# Audio_Codec.net
KiCad netlist of a schematic drawn in Altium Designer
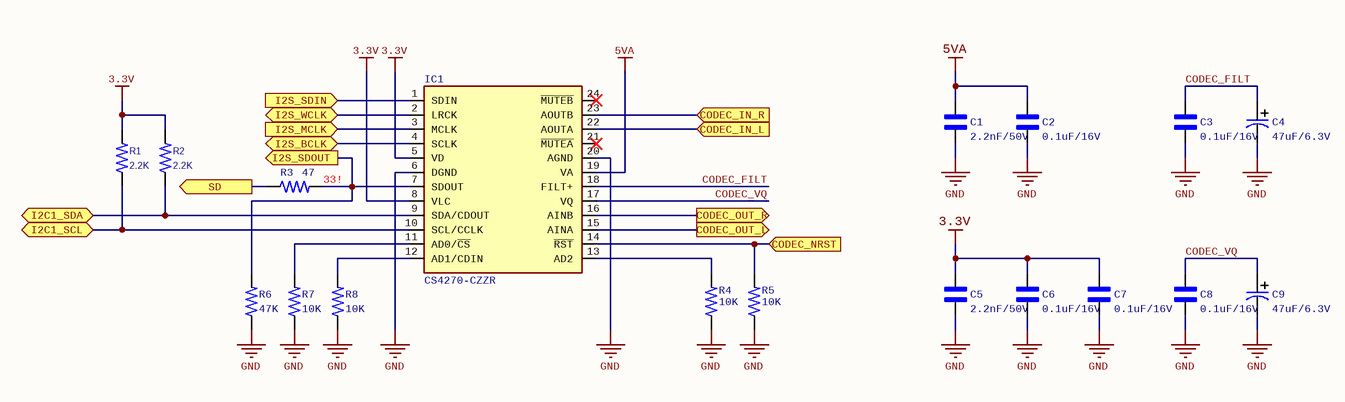
[diagram p0: Audio Codec.SchDoc]

(export (version "E")
  (design (tool "Eeschema 10.0.6"))
  (components
    (comp (ref "C1")
      (value "2.2nF/50V")
      (footprint "C0603")
      (description "MLCC 2.2nF 10V X5R 10% 0603")
      (fields
        (field (name "MANUFACTURER") "Samsung")
        (field (name "MANUFACTURER PART NUMBER") "CL10B222KB8NFNC")
      )
      (libsource (lib "Capacitors") (part "C0603 2.2nF/50V"))
    )
    (comp (ref "C2")
      (value "0.1uF/16V")
      (footprint "C0603")
      (description "MLCC 0.1UF, 16V, X5R, 10%, 0603.")
      (fields
        (field (name "MANUFACTURER") "Kyocera AVX")
        (field (name "MANUFACTURER PART NUMBER") "0603YD104KAT2A")
      )
      (libsource (lib "Capacitors") (part "C0603 0.1uF/16V"))
    )
    (comp (ref "C3")
      (value "0.1uF/16V")
      (footprint "C0603")
      (description "MLCC 0.1UF, 16V, X5R, 10%, 0603.")
      (fields
        (field (name "MANUFACTURER") "Kyocera AVX")
        (field (name "MANUFACTURER PART NUMBER") "0603YD104KAT2A")
      )
      (libsource (lib "Capacitors") (part "C0603 0.1uF/16V"))
    )
    (comp (ref "C4")
      (value "47uF/6.3V")
      (footprint "EIA1206")
      (description "Tantalum Capacitors - Solid SMD 6.3V 47uF 10%")
      (fields
        (field (name "MANUFACTURER") "Kyocera AVX")
        (field (name "MANUFACTURER PART NUMBER") "TAJA476K006SNJV")
      )
      (libsource (lib "Capacitors") (part "TANT 47UF/6.3V"))
    )
    (comp (ref "C5")
      (value "2.2nF/50V")
      (footprint "C0603")
      (description "MLCC 2.2nF 10V X5R 10% 0603")
      (fields
        (field (name "MANUFACTURER") "Samsung")
        (field (name "MANUFACTURER PART NUMBER") "CL10B222KB8NFNC")
      )
      (libsource (lib "Capacitors") (part "C0603 2.2nF/50V"))
    )
    (comp (ref "C6")
      (value "0.1uF/16V")
      (footprint "C0603")
      (description "MLCC 0.1UF, 16V, X5R, 10%, 0603.")
      (fields
        (field (name "MANUFACTURER") "Kyocera AVX")
        (field (name "MANUFACTURER PART NUMBER") "0603YD104KAT2A")
      )
      (libsource (lib "Capacitors") (part "C0603 0.1uF/16V"))
    )
    (comp (ref "C7")
      (value "0.1uF/16V")
      (footprint "C0603")
      (description "MLCC 0.1UF, 16V, X5R, 10%, 0603.")
      (fields
        (field (name "MANUFACTURER") "Kyocera AVX")
        (field (name "MANUFACTURER PART NUMBER") "0603YD104KAT2A")
      )
      (libsource (lib "Capacitors") (part "C0603 0.1uF/16V"))
    )
    (comp (ref "C8")
      (value "0.1uF/16V")
      (footprint "C0603")
      (description "MLCC 0.1UF, 16V, X5R, 10%, 0603.")
      (fields
        (field (name "MANUFACTURER") "Kyocera AVX")
        (field (name "MANUFACTURER PART NUMBER") "0603YD104KAT2A")
      )
      (libsource (lib "Capacitors") (part "C0603 0.1uF/16V"))
    )
    (comp (ref "C9")
      (value "47uF/6.3V")
      (footprint "EIA1206")
      (description "Tantalum Capacitors - Solid SMD 6.3V 47uF 10%")
      (fields
        (field (name "MANUFACTURER") "Kyocera AVX")
        (field (name "MANUFACTURER PART NUMBER") "TAJA476K006SNJV")
      )
      (libsource (lib "Capacitors") (part "TANT 47UF/6.3V"))
    )
    (comp (ref "IC1")
      (value "CS4270-CZZR")
      (footprint "TSSOP-24")
      (description "Audio Codec 2ADC / 2DAC 24-Bit 24-Pin TSSOP T/R (Alt: CS4270-CZZR)")
      (fields (field (name "MANUFACTURER") "Cirrus Logic"))
      (libsource (lib "IC Converter") (part "CS4270-CZZR"))
    )
    (comp (ref "R1")
      (value "2.2K")
      (footprint "R0603")
      (description "RES 0603 2.2K OHM 1% 1/10W")
      (fields
        (field (name "MANUFACTURER") "Yageo")
        (field (name "MANUFACTURER PART NUMBER") "RC0603FR-072K2L")
      )
      (libsource (lib "Resistors") (part "R0603 2.2K"))
    )
    (comp (ref "R2")
      (value "2.2K")
      (footprint "R0603")
      (description "RES 0603 2.2K OHM 1% 1/10W")
      (fields
        (field (name "MANUFACTURER") "Yageo")
        (field (name "MANUFACTURER PART NUMBER") "RC0603FR-072K2L")
      )
      (libsource (lib "Resistors") (part "R0603 2.2K"))
    )
    (comp (ref "R3")
      (value "47")
      (footprint "R0603")
      (description "RES 0603 47 1% 1/10W")
      (fields
        (field (name "MANUFACTURER") "Yageo")
        (field (name "MANUFACTURER PART NUMBER") "RC0603FR-0747RL")
      )
      (libsource (lib "Resistors") (part "R0603 47"))
    )
    (comp (ref "R4")
      (value "10K")
      (footprint "R0603")
      (description "RES 0603 10K OHM 1% 1/10W")
      (fields
        (field (name "MANUFACTURER") "Yageo")
        (field (name "MANUFACTURER PART NUMBER") "RC0603FR-0710KP")
      )
      (libsource (lib "Resistors") (part "R0603 10K"))
    )
    (comp (ref "R5")
      (value "10K")
      (footprint "R0603")
      (description "RES 0603 10K OHM 1% 1/10W")
      (fields
        (field (name "MANUFACTURER") "Yageo")
        (field (name "MANUFACTURER PART NUMBER") "RC0603FR-0710KP")
      )
      (libsource (lib "Resistors") (part "R0603 10K"))
    )
    (comp (ref "R6")
      (value "47K")
      (footprint "R0603")
      (description "RES 0603 47K 1% 1/10W")
      (fields
        (field (name "MANUFACTURER") "Yageo")
        (field (name "MANUFACTURER PART NUMBER") "RC0603FR-0747KL")
      )
      (libsource (lib "Resistors") (part "R0603 47K"))
    )
    (comp (ref "R7")
      (value "10K")
      (footprint "R0603")
      (description "RES 0603 10K OHM 1% 1/10W")
      (fields
        (field (name "MANUFACTURER") "Yageo")
        (field (name "MANUFACTURER PART NUMBER") "RC0603FR-0710KP")
      )
      (libsource (lib "Resistors") (part "R0603 10K"))
    )
    (comp (ref "R8")
      (value "10K")
      (footprint "R0603")
      (description "RES 0603 10K OHM 1% 1/10W")
      (fields
        (field (name "MANUFACTURER") "Yageo")
        (field (name "MANUFACTURER PART NUMBER") "RC0603FR-0710KP")
      )
      (libsource (lib "Resistors") (part "R0603 10K"))
    )
  )
  (nets
    (net (code "1") (name "/CODEC_FILT") (class "Default")
      (node (ref "C3") (pin "2") (pinfunction "2_2") (pintype "passive"))
      (node (ref "C4") (pin "1") (pinfunction "1_1") (pintype "passive"))
      (node (ref "IC1") (pin "18") (pinfunction "FILT+_18") (pintype "passive"))
    )
    (net (code "2") (name "/CODEC_IN_L") (class "Default")
      (node (ref "IC1") (pin "22") (pinfunction "AOUTA_22") (pintype "passive"))
    )
    (net (code "3") (name "/CODEC_IN_R") (class "Default")
      (node (ref "IC1") (pin "23") (pinfunction "AOUTB_23") (pintype "passive"))
    )
    (net (code "4") (name "/CODEC_NRST") (class "Default")
      (node (ref "IC1") (pin "14") (pinfunction "~{RST}_14") (pintype "passive"))
      (node (ref "R5") (pin "2") (pinfunction "2_2") (pintype "passive"))
    )
    (net (code "5") (name "/CODEC_OUT_L") (class "Default")
      (node (ref "IC1") (pin "15") (pinfunction "AINA_15") (pintype "passive"))
    )
    (net (code "6") (name "/CODEC_OUT_R") (class "Default")
      (node (ref "IC1") (pin "16") (pinfunction "AINB_16") (pintype "passive"))
    )
    (net (code "7") (name "/CODEC_VQ") (class "Default")
      (node (ref "C8") (pin "2") (pinfunction "2_2") (pintype "passive"))
      (node (ref "C9") (pin "1") (pinfunction "1_1") (pintype "passive"))
      (node (ref "IC1") (pin "17") (pinfunction "VQ_17") (pintype "passive"))
    )
    (net (code "8") (name "/I2C1_SCL") (class "Default")
      (node (ref "IC1") (pin "10") (pinfunction "SCL/CCLK_10") (pintype "passive"))
      (node (ref "R1") (pin "1") (pinfunction "1_1") (pintype "passive"))
    )
    (net (code "9") (name "/I2C1_SDA") (class "Default")
      (node (ref "IC1") (pin "9") (pinfunction "SDA/CDOUT_9") (pintype "passive"))
      (node (ref "R2") (pin "1") (pinfunction "1_1") (pintype "passive"))
    )
    (net (code "10") (name "/I2S_BCLK") (class "Default")
      (node (ref "IC1") (pin "4") (pinfunction "SCLK_4") (pintype "passive"))
    )
    (net (code "11") (name "/I2S_MCLK") (class "Default")
      (node (ref "IC1") (pin "3") (pinfunction "MCLK_3") (pintype "passive"))
    )
    (net (code "12") (name "/I2S_SDIN") (class "Default")
      (node (ref "IC1") (pin "1") (pinfunction "SDIN_1") (pintype "passive"))
    )
    (net (code "13") (name "/I2S_SDOUT") (class "Default")
      (node (ref "IC1") (pin "7") (pinfunction "SDOUT_7") (pintype "passive"))
      (node (ref "R3") (pin "2") (pinfunction "2_2") (pintype "passive"))
      (node (ref "R6") (pin "2") (pinfunction "2_2") (pintype "passive"))
    )
    (net (code "14") (name "/I2S_WCLK") (class "Default")
      (node (ref "IC1") (pin "2") (pinfunction "LRCK_2") (pintype "passive"))
    )
    (net (code "15") (name "/SD") (class "Default")
      (node (ref "R3") (pin "1") (pinfunction "1_1") (pintype "passive"))
    )
    (net (code "16") (name "3.3V") (class "Default")
      (node (ref "C5") (pin "1") (pinfunction "1_1") (pintype "passive"))
      (node (ref "C6") (pin "2") (pinfunction "2_2") (pintype "passive"))
      (node (ref "C7") (pin "2") (pinfunction "2_2") (pintype "passive"))
      (node (ref "IC1") (pin "5") (pinfunction "VD_5") (pintype "passive"))
      (node (ref "IC1") (pin "8") (pinfunction "VLC_8") (pintype "passive"))
      (node (ref "R1") (pin "2") (pinfunction "2_2") (pintype "passive"))
      (node (ref "R2") (pin "2") (pinfunction "2_2") (pintype "passive"))
    )
    (net (code "17") (name "5VA") (class "Default")
      (node (ref "C1") (pin "1") (pinfunction "1_1") (pintype "passive"))
      (node (ref "C2") (pin "2") (pinfunction "2_2") (pintype "passive"))
      (node (ref "IC1") (pin "19") (pinfunction "VA_19") (pintype "passive"))
    )
    (net (code "18") (name "GND") (class "Default")
      (node (ref "C1") (pin "2") (pinfunction "2_2") (pintype "passive"))
      (node (ref "C2") (pin "1") (pinfunction "1_1") (pintype "passive"))
      (node (ref "C3") (pin "1") (pinfunction "1_1") (pintype "passive"))
      (node (ref "C4") (pin "2") (pinfunction "2_2") (pintype "passive"))
      (node (ref "C5") (pin "2") (pinfunction "2_2") (pintype "passive"))
      (node (ref "C6") (pin "1") (pinfunction "1_1") (pintype "passive"))
      (node (ref "C7") (pin "1") (pinfunction "1_1") (pintype "passive"))
      (node (ref "C8") (pin "1") (pinfunction "1_1") (pintype "passive"))
      (node (ref "C9") (pin "2") (pinfunction "2_2") (pintype "passive"))
      (node (ref "IC1") (pin "20") (pinfunction "AGND_20") (pintype "passive"))
      (node (ref "IC1") (pin "6") (pinfunction "DGND_6") (pintype "passive"))
      (node (ref "R4") (pin "1") (pinfunction "1_1") (pintype "passive"))
      (node (ref "R5") (pin "1") (pinfunction "1_1") (pintype "passive"))
      (node (ref "R6") (pin "1") (pinfunction "1_1") (pintype "passive"))
      (node (ref "R7") (pin "1") (pinfunction "1_1") (pintype "passive"))
      (node (ref "R8") (pin "1") (pinfunction "1_1") (pintype "passive"))
    )
    (net (code "19") (name "Net-(IC1-AD0{slash}~{CS})") (class "Default")
      (node (ref "IC1") (pin "11") (pinfunction "AD0/~{CS}_11") (pintype "passive"))
      (node (ref "R7") (pin "2") (pinfunction "2_2") (pintype "passive"))
    )
    (net (code "20") (name "Net-(IC1-AD1{slash}CDIN)") (class "Default")
      (node (ref "IC1") (pin "12") (pinfunction "AD1/CDIN_12") (pintype "passive"))
      (node (ref "R8") (pin "2") (pinfunction "2_2") (pintype "passive"))
    )
    (net (code "21") (name "Net-(IC1-AD2)") (class "Default")
      (node (ref "IC1") (pin "13") (pinfunction "AD2_13") (pintype "passive"))
      (node (ref "R4") (pin "2") (pinfunction "2_2") (pintype "passive"))
    )
    (net (code "22") (name "unconnected-(IC1-~{MUTEA}-Pad21)") (class "Default")
      (node (ref "IC1") (pin "21") (pinfunction "~{MUTEA}_21") (pintype "passive+no_connect"))
    )
    (net (code "23") (name "unconnected-(IC1-~{MUTEB}-Pad24)") (class "Default")
      (node (ref "IC1") (pin "24") (pinfunction "~{MUTEB}_24") (pintype "passive+no_connect"))
    )
  )
)
